# modbrainsv0_4_3.net
KiCad netlist of a schematic drawn in EAGLE
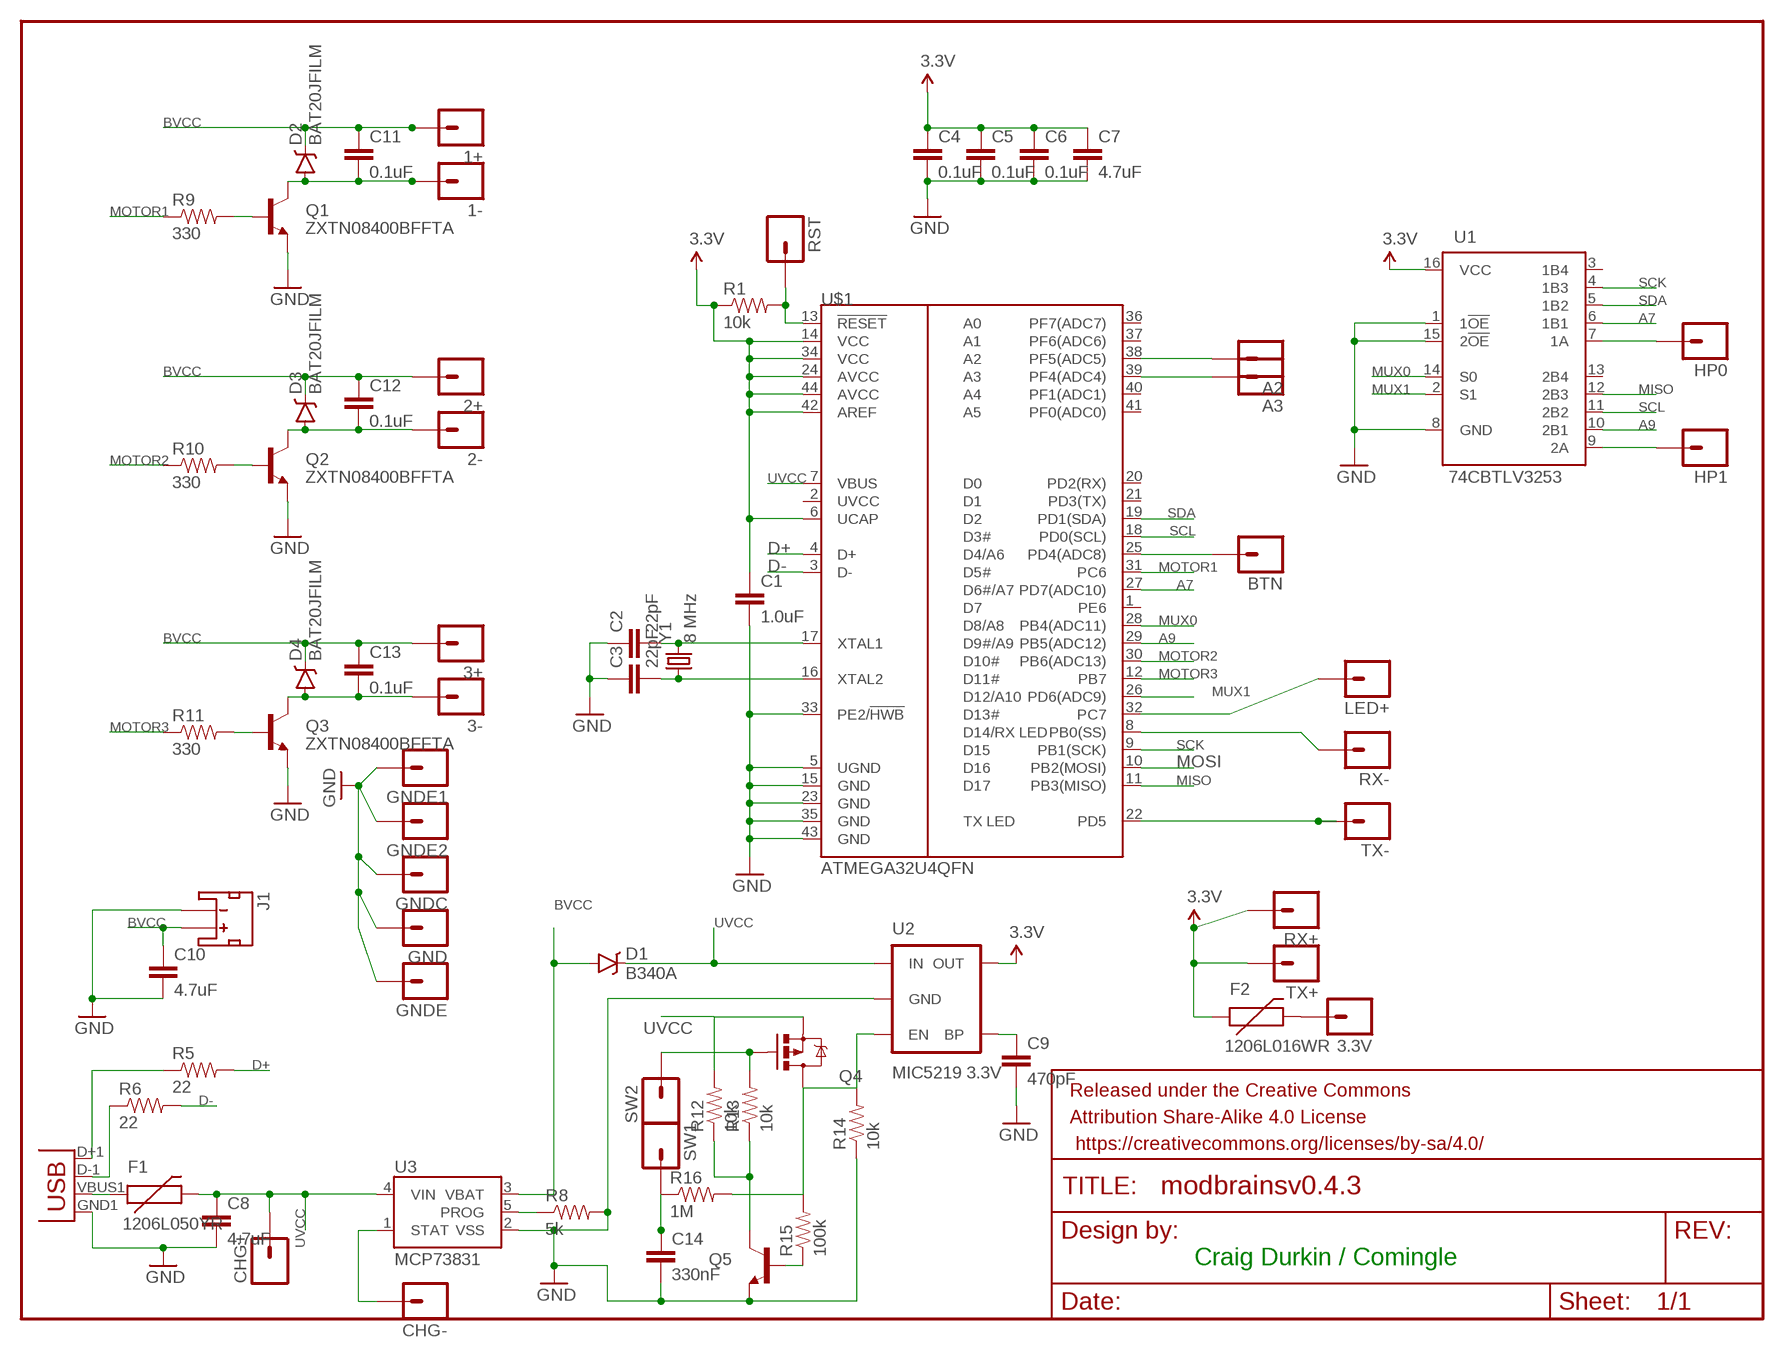
[diagram p0: schematic, sheet 1]

(export (version "E")
  (design (tool "Eeschema 10.0.6"))
  (components
    (comp (ref "1+")
      (value "M01PTH")
      (footprint "eagle-import:1X01")
      (libsource (lib "eagle-import") (part "M01PTH"))
    )
    (comp (ref "1-")
      (value "M01PTH")
      (footprint "eagle-import:1X01")
      (libsource (lib "eagle-import") (part "M01PTH"))
    )
    (comp (ref "2+")
      (value "M01PTH")
      (footprint "eagle-import:1X01")
      (libsource (lib "eagle-import") (part "M01PTH"))
    )
    (comp (ref "2-")
      (value "M01PTH")
      (footprint "eagle-import:1X01")
      (libsource (lib "eagle-import") (part "M01PTH"))
    )
    (comp (ref "3+")
      (value "M01PTH")
      (footprint "eagle-import:1X01")
      (libsource (lib "eagle-import") (part "M01PTH"))
    )
    (comp (ref "3-")
      (value "M01PTH")
      (footprint "eagle-import:1X01")
      (libsource (lib "eagle-import") (part "M01PTH"))
    )
    (comp (ref "3.3V")
      (value "M01PTH")
      (footprint "eagle-import:1X01")
      (libsource (lib "eagle-import") (part "M01PTH"))
    )
    (comp (ref "A2")
      (value "M01PTH")
      (footprint "eagle-import:1X01")
      (libsource (lib "eagle-import") (part "M01PTH"))
    )
    (comp (ref "A3")
      (value "M01PTH")
      (footprint "eagle-import:1X01")
      (libsource (lib "eagle-import") (part "M01PTH"))
    )
    (comp (ref "BTN")
      (value "M01PTH")
      (footprint "eagle-import:1X01")
      (libsource (lib "eagle-import") (part "M01PTH"))
    )
    (comp (ref "C1")
      (value "1.0uF")
      (footprint "eagle-import:0603-CAP")
      (libsource (lib "eagle-import") (part "CAP0603-CAP"))
    )
    (comp (ref "C2")
      (value "22pF")
      (footprint "eagle-import:0603-CAP")
      (libsource (lib "eagle-import") (part "CAP0603-CAP"))
    )
    (comp (ref "C3")
      (value "22pF")
      (footprint "eagle-import:0603-CAP")
      (libsource (lib "eagle-import") (part "CAP0603-CAP"))
    )
    (comp (ref "C4")
      (value "0.1uF")
      (footprint "eagle-import:0603-CAP")
      (libsource (lib "eagle-import") (part "SparkFun-Passives_CAP0603-CAP"))
    )
    (comp (ref "C5")
      (value "0.1uF")
      (footprint "eagle-import:0603-CAP")
      (libsource (lib "eagle-import") (part "SparkFun-Passives_CAP0603-CAP"))
    )
    (comp (ref "C6")
      (value "0.1uF")
      (footprint "eagle-import:0603-CAP")
      (libsource (lib "eagle-import") (part "SparkFun-Passives_CAP0603-CAP"))
    )
    (comp (ref "C7")
      (value "4.7uF")
      (footprint "eagle-import:0603-CAP")
      (libsource (lib "eagle-import") (part "SparkFun-Passives_CAP0603-CAP"))
    )
    (comp (ref "C8")
      (value "4.7uF")
      (footprint "eagle-import:1206")
      (libsource (lib "eagle-import") (part "SparkFun-Passives_CAP1206"))
    )
    (comp (ref "C9")
      (value "470pF")
      (footprint "eagle-import:0603-CAP")
      (libsource (lib "eagle-import") (part "CAP0603-CAP"))
    )
    (comp (ref "C10")
      (value "4.7uF")
      (footprint "eagle-import:1206")
      (libsource (lib "eagle-import") (part "SparkFun-Passives_CAP1206"))
    )
    (comp (ref "C11")
      (value "0.1uF")
      (footprint "eagle-import:0603-CAP")
      (libsource (lib "eagle-import") (part "CAP0603-CAP"))
    )
    (comp (ref "C12")
      (value "0.1uF")
      (footprint "eagle-import:0603-CAP")
      (libsource (lib "eagle-import") (part "CAP0603-CAP"))
    )
    (comp (ref "C13")
      (value "0.1uF")
      (footprint "eagle-import:0603-CAP")
      (libsource (lib "eagle-import") (part "CAP0603-CAP"))
    )
    (comp (ref "C14")
      (value "330nF")
      (footprint "eagle-import:0603-CAP")
      (libsource (lib "eagle-import") (part "CAP0603-CAP"))
    )
    (comp (ref "CHG+")
      (value "M01PTH")
      (footprint "eagle-import:1X01")
      (libsource (lib "eagle-import") (part "M01PTH"))
    )
    (comp (ref "CHG-")
      (value "M01PTH")
      (footprint "eagle-import:1X01")
      (libsource (lib "eagle-import") (part "M01PTH"))
    )
    (comp (ref "D1")
      (value "B340A")
      (footprint "eagle-import:SMA-DIODE")
      (libsource (lib "eagle-import") (part "DIODE-SCHOTTKY-B340A"))
    )
    (comp (ref "D2")
      (value "BAT20JFILM")
      (footprint "eagle-import:SOD-323")
      (libsource (lib "eagle-import") (part "BAT20JFILM"))
    )
    (comp (ref "D3")
      (value "BAT20JFILM")
      (footprint "eagle-import:SOD-323")
      (libsource (lib "eagle-import") (part "BAT20JFILM"))
    )
    (comp (ref "D4")
      (value "BAT20JFILM")
      (footprint "eagle-import:SOD-323")
      (libsource (lib "eagle-import") (part "BAT20JFILM"))
    )
    (comp (ref "F1")
      (value "1206L050YR")
      (footprint "eagle-import:PTC-1206")
      (libsource (lib "eagle-import") (part "PTCSMD"))
    )
    (comp (ref "F2")
      (value "1206L016WR")
      (footprint "eagle-import:PTC-1206")
      (libsource (lib "eagle-import") (part "PTCSMD"))
    )
    (comp (ref "FRAME1")
      (value "FRAME-LETTER")
      (footprint "eagle-import:CREATIVE_COMMONS")
      (libsource (lib "eagle-import") (part "FRAME-LETTER"))
    )
    (comp (ref "GND")
      (value "M01PTH")
      (footprint "eagle-import:1X01")
      (libsource (lib "eagle-import") (part "M01PTH"))
    )
    (comp (ref "GNDC")
      (value "M01PTH")
      (footprint "eagle-import:1X01")
      (libsource (lib "eagle-import") (part "M01PTH"))
    )
    (comp (ref "GNDE")
      (value "M01PTH")
      (footprint "eagle-import:1X01")
      (libsource (lib "eagle-import") (part "M01PTH"))
    )
    (comp (ref "GNDE1")
      (value "M01PTH")
      (footprint "eagle-import:1X01")
      (libsource (lib "eagle-import") (part "M01PTH"))
    )
    (comp (ref "GNDE2")
      (value "M01PTH")
      (footprint "eagle-import:1X01")
      (libsource (lib "eagle-import") (part "M01PTH"))
    )
    (comp (ref "HP0")
      (value "M01PTH")
      (footprint "eagle-import:1X01")
      (libsource (lib "eagle-import") (part "M01PTH"))
    )
    (comp (ref "HP1")
      (value "M01PTH")
      (footprint "eagle-import:1X01")
      (libsource (lib "eagle-import") (part "M01PTH"))
    )
    (comp (ref "J1")
      (value "JST_2MM_MALE")
      (footprint "eagle-import:JST-2-SMD")
      (libsource (lib "eagle-import") (part "JST_2MM_MALE"))
    )
    (comp (ref "JP4")
      (value "USB")
      (footprint "eagle-import:USB-B-MICRO-SMD_V03")
      (libsource (lib "eagle-import") (part "USB"))
    )
    (comp (ref "LED+")
      (value "M01PTH")
      (footprint "eagle-import:1X01")
      (libsource (lib "eagle-import") (part "M01PTH"))
    )
    (comp (ref "Q1")
      (value "ZXTN08400BFFTA")
      (footprint "eagle-import:SOT23-3")
      (libsource (lib "eagle-import") (part "TRANSISTOR_NPNSOT23-3"))
    )
    (comp (ref "Q2")
      (value "ZXTN08400BFFTA")
      (footprint "eagle-import:SOT23-3")
      (libsource (lib "eagle-import") (part "TRANSISTOR_NPNSOT23-3"))
    )
    (comp (ref "Q3")
      (value "ZXTN08400BFFTA")
      (footprint "eagle-import:SOT23-3")
      (libsource (lib "eagle-import") (part "TRANSISTOR_NPNSOT23-3"))
    )
    (comp (ref "Q4")
      (value "NTS2101PT1G")
      (footprint "eagle-import:SOT23-3")
      (libsource (lib "eagle-import") (part "MOSFET-PCHANNEL"))
    )
    (comp (ref "Q5")
      (value "MMBT2222A")
      (footprint "eagle-import:SOT23-3")
      (libsource (lib "eagle-import") (part "TRANSISTOR_NPNMMBT2222A"))
    )
    (comp (ref "R1")
      (value "10k")
      (footprint "eagle-import:0603-RES")
      (libsource (lib "eagle-import") (part "RESISTOR0603-RES"))
    )
    (comp (ref "R5")
      (value "22")
      (footprint "eagle-import:0603-RES")
      (libsource (lib "eagle-import") (part "RESISTOR0603-RES"))
    )
    (comp (ref "R6")
      (value "22")
      (footprint "eagle-import:0603-RES")
      (libsource (lib "eagle-import") (part "RESISTOR0603-RES"))
    )
    (comp (ref "R8")
      (value "5k")
      (footprint "eagle-import:0603-RES")
      (libsource (lib "eagle-import") (part "RESISTOR0603-RES"))
    )
    (comp (ref "R9")
      (value "330")
      (footprint "eagle-import:0603-RES")
      (libsource (lib "eagle-import") (part "RESISTOR0603-RES"))
    )
    (comp (ref "R10")
      (value "330")
      (footprint "eagle-import:0603-RES")
      (libsource (lib "eagle-import") (part "RESISTOR0603-RES"))
    )
    (comp (ref "R11")
      (value "330")
      (footprint "eagle-import:0603-RES")
      (libsource (lib "eagle-import") (part "RESISTOR0603-RES"))
    )
    (comp (ref "R12")
      (value "10k")
      (footprint "eagle-import:0603-RES")
      (libsource (lib "eagle-import") (part "RESISTOR0603-RES"))
    )
    (comp (ref "R13")
      (value "10k")
      (footprint "eagle-import:0603-RES")
      (libsource (lib "eagle-import") (part "RESISTOR0603-RES"))
    )
    (comp (ref "R14")
      (value "10k")
      (footprint "eagle-import:0603-RES")
      (libsource (lib "eagle-import") (part "RESISTOR0603-RES"))
    )
    (comp (ref "R15")
      (value "100k")
      (footprint "eagle-import:0603-RES")
      (libsource (lib "eagle-import") (part "RESISTOR0603-RES"))
    )
    (comp (ref "R16")
      (value "1M")
      (footprint "eagle-import:0603-RES")
      (libsource (lib "eagle-import") (part "RESISTOR0603-RES"))
    )
    (comp (ref "RST")
      (value "M01PTH")
      (footprint "eagle-import:1X01")
      (libsource (lib "eagle-import") (part "M01PTH"))
    )
    (comp (ref "RX+")
      (value "M01PTH")
      (footprint "eagle-import:1X01")
      (libsource (lib "eagle-import") (part "M01PTH"))
    )
    (comp (ref "RX-")
      (value "M01PTH")
      (footprint "eagle-import:1X01")
      (libsource (lib "eagle-import") (part "M01PTH"))
    )
    (comp (ref "SW1")
      (value "M01PTH")
      (footprint "eagle-import:1X01")
      (libsource (lib "eagle-import") (part "M01PTH"))
    )
    (comp (ref "SW2")
      (value "M01PTH")
      (footprint "eagle-import:1X01")
      (libsource (lib "eagle-import") (part "M01PTH"))
    )
    (comp (ref "TX+")
      (value "M01PTH")
      (footprint "eagle-import:1X01")
      (libsource (lib "eagle-import") (part "M01PTH"))
    )
    (comp (ref "TX-")
      (value "M01PTH")
      (footprint "eagle-import:1X01")
      (libsource (lib "eagle-import") (part "M01PTH"))
    )
    (comp (ref "U$1")
      (value "ATMEGA32U4QFN")
      (footprint "eagle-import:QFN-44")
      (libsource (lib "eagle-import") (part "ATMEGA32U4QFN"))
    )
    (comp (ref "U1")
      (value "74CBTLV3253")
      (footprint "eagle-import:SSOP16-PRACTICE")
      (libsource (lib "eagle-import") (part "74CBTLV3253"))
    )
    (comp (ref "U2")
      (value "MIC5219 3.3V")
      (footprint "eagle-import:SOT23-5")
      (libsource (lib "eagle-import") (part "V_REG_MIC52193.3V"))
    )
    (comp (ref "U3")
      (value "MCP73831")
      (footprint "eagle-import:SOT23-5")
      (libsource (lib "eagle-import") (part "MCP73831"))
    )
    (comp (ref "Y1")
      (value "8 MHz")
      (footprint "eagle-import:CRYSTAL-SMD-5X3")
      (libsource (lib "eagle-import") (part "CRYSTAL5X3"))
    )
  )
  (nets
    (net (code "1") (name "/A7") (class "Default")
      (node (ref "U$1") (pin "27") (pinfunction "PD7(ADC10)_27") (pintype "bidirectional"))
      (node (ref "U1") (pin "6") (pinfunction "1B1_6") (pintype "bidirectional"))
    )
    (net (code "2") (name "/A9") (class "Default")
      (node (ref "U$1") (pin "29") (pinfunction "PB5(ADC12)_29") (pintype "bidirectional"))
      (node (ref "U1") (pin "10") (pinfunction "2B1_10") (pintype "bidirectional"))
    )
    (net (code "3") (name "/BVCC") (class "Default")
      (node (ref "1+") (pin "1") (pinfunction "1_1") (pintype "passive"))
      (node (ref "2+") (pin "1") (pinfunction "1_1") (pintype "passive"))
      (node (ref "3+") (pin "1") (pinfunction "1_1") (pintype "passive"))
      (node (ref "C10") (pin "1") (pinfunction "1_1") (pintype "passive"))
      (node (ref "C11") (pin "1") (pinfunction "1_1") (pintype "passive"))
      (node (ref "C12") (pin "1") (pinfunction "1_1") (pintype "passive"))
      (node (ref "C13") (pin "1") (pinfunction "1_1") (pintype "passive"))
      (node (ref "D1") (pin "A") (pinfunction "A_A") (pintype "passive"))
      (node (ref "D2") (pin "C") (pinfunction "C_C") (pintype "passive"))
      (node (ref "D3") (pin "C") (pinfunction "C_C") (pintype "passive"))
      (node (ref "D4") (pin "C") (pinfunction "C_C") (pintype "passive"))
      (node (ref "J1") (pin "2") (pinfunction "+_2") (pintype "bidirectional"))
      (node (ref "U3") (pin "3") (pinfunction "VBAT_3") (pintype "power_in"))
    )
    (net (code "4") (name "/D+") (class "Default")
      (node (ref "R5") (pin "2") (pinfunction "2_2") (pintype "passive"))
      (node (ref "U$1") (pin "4") (pinfunction "D+_4") (pintype "bidirectional"))
    )
    (net (code "5") (name "/D-") (class "Default")
      (node (ref "R6") (pin "2") (pinfunction "2_2") (pintype "passive"))
      (node (ref "U$1") (pin "3") (pinfunction "D-_3") (pintype "bidirectional"))
    )
    (net (code "6") (name "/MISO") (class "Default")
      (node (ref "U$1") (pin "11") (pinfunction "PB3(MISO)_11") (pintype "bidirectional"))
      (node (ref "U1") (pin "12") (pinfunction "2B3_12") (pintype "bidirectional"))
    )
    (net (code "7") (name "/MOSI") (class "Default")
      (node (ref "U$1") (pin "10") (pinfunction "PB2(MOSI)_10") (pintype "bidirectional"))
    )
    (net (code "8") (name "/MOTOR1") (class "Default")
      (node (ref "R9") (pin "1") (pinfunction "1_1") (pintype "passive"))
      (node (ref "U$1") (pin "31") (pinfunction "PC6_31") (pintype "bidirectional"))
    )
    (net (code "9") (name "/MOTOR2") (class "Default")
      (node (ref "R10") (pin "1") (pinfunction "1_1") (pintype "passive"))
      (node (ref "U$1") (pin "30") (pinfunction "PB6(ADC13)_30") (pintype "bidirectional"))
    )
    (net (code "10") (name "/MOTOR3") (class "Default")
      (node (ref "R11") (pin "1") (pinfunction "1_1") (pintype "passive"))
      (node (ref "U$1") (pin "12") (pinfunction "PB7_12") (pintype "bidirectional"))
    )
    (net (code "11") (name "/MUX0") (class "Default")
      (node (ref "U$1") (pin "28") (pinfunction "PB4(ADC11)_28") (pintype "bidirectional"))
      (node (ref "U1") (pin "14") (pinfunction "S0_14") (pintype "bidirectional"))
    )
    (net (code "12") (name "/MUX1") (class "Default")
      (node (ref "U$1") (pin "26") (pinfunction "PD6(ADC9)_26") (pintype "bidirectional"))
      (node (ref "U1") (pin "2") (pinfunction "S1_2") (pintype "bidirectional"))
    )
    (net (code "13") (name "/SCK") (class "Default")
      (node (ref "U$1") (pin "9") (pinfunction "PB1(SCK)_9") (pintype "bidirectional"))
      (node (ref "U1") (pin "4") (pinfunction "1B3_4") (pintype "bidirectional"))
    )
    (net (code "14") (name "/SCL") (class "Default")
      (node (ref "U$1") (pin "18") (pinfunction "PD0(SCL)_18") (pintype "bidirectional"))
      (node (ref "U1") (pin "11") (pinfunction "2B2_11") (pintype "bidirectional"))
    )
    (net (code "15") (name "/SDA") (class "Default")
      (node (ref "U$1") (pin "19") (pinfunction "PD1(SDA)_19") (pintype "bidirectional"))
      (node (ref "U1") (pin "5") (pinfunction "1B2_5") (pintype "bidirectional"))
    )
    (net (code "16") (name "/UVCC") (class "Default")
      (node (ref "C8") (pin "1") (pinfunction "1_1") (pintype "passive"))
      (node (ref "CHG+") (pin "1") (pinfunction "1_1") (pintype "passive"))
      (node (ref "D1") (pin "C") (pinfunction "C_C") (pintype "passive"))
      (node (ref "F1") (pin "2") (pinfunction "2_2") (pintype "bidirectional"))
      (node (ref "Q4") (pin "2") (pinfunction "S_2") (pintype "passive"))
      (node (ref "R12") (pin "2") (pinfunction "2_2") (pintype "passive"))
      (node (ref "U$1") (pin "7") (pinfunction "VBUS_7") (pintype "bidirectional"))
      (node (ref "U2") (pin "1") (pinfunction "IN_1") (pintype "input"))
      (node (ref "U3") (pin "4") (pinfunction "VIN_4") (pintype "power_in"))
    )
    (net (code "17") (name "3.3V") (class "Default")
      (node (ref "C1") (pin "1") (pinfunction "1_1") (pintype "passive"))
      (node (ref "C4") (pin "1") (pinfunction "1_1") (pintype "passive"))
      (node (ref "C5") (pin "1") (pinfunction "1_1") (pintype "passive"))
      (node (ref "C6") (pin "1") (pinfunction "1_1") (pintype "passive"))
      (node (ref "C7") (pin "1") (pinfunction "1_1") (pintype "passive"))
      (node (ref "F2") (pin "1") (pinfunction "1_1") (pintype "bidirectional"))
      (node (ref "R1") (pin "1") (pinfunction "1_1") (pintype "passive"))
      (node (ref "RX+") (pin "1") (pinfunction "1_1") (pintype "passive"))
      (node (ref "TX+") (pin "1") (pinfunction "1_1") (pintype "passive"))
      (node (ref "U$1") (pin "14") (pinfunction "VCC_14") (pintype "bidirectional"))
      (node (ref "U$1") (pin "24") (pinfunction "AVCC_24") (pintype "bidirectional"))
      (node (ref "U$1") (pin "34") (pinfunction "VCC_34") (pintype "bidirectional"))
      (node (ref "U$1") (pin "42") (pinfunction "AREF_42") (pintype "bidirectional"))
      (node (ref "U$1") (pin "44") (pinfunction "AVCC_44") (pintype "bidirectional"))
      (node (ref "U$1") (pin "6") (pinfunction "UCAP_6") (pintype "bidirectional"))
      (node (ref "U1") (pin "16") (pinfunction "VCC_16") (pintype "power_in"))
      (node (ref "U2") (pin "5") (pinfunction "OUT_5") (pintype "passive"))
    )
    (net (code "18") (name "GND") (class "Default")
      (node (ref "C1") (pin "2") (pinfunction "2_2") (pintype "passive"))
      (node (ref "C10") (pin "2") (pinfunction "2_2") (pintype "passive"))
      (node (ref "C14") (pin "2") (pinfunction "2_2") (pintype "passive"))
      (node (ref "C2") (pin "1") (pinfunction "1_1") (pintype "passive"))
      (node (ref "C3") (pin "1") (pinfunction "1_1") (pintype "passive"))
      (node (ref "C4") (pin "2") (pinfunction "2_2") (pintype "passive"))
      (node (ref "C5") (pin "2") (pinfunction "2_2") (pintype "passive"))
      (node (ref "C6") (pin "2") (pinfunction "2_2") (pintype "passive"))
      (node (ref "C7") (pin "2") (pinfunction "2_2") (pintype "passive"))
      (node (ref "C8") (pin "2") (pinfunction "2_2") (pintype "passive"))
      (node (ref "C9") (pin "2") (pinfunction "2_2") (pintype "passive"))
      (node (ref "GND") (pin "1") (pinfunction "1_1") (pintype "passive"))
      (node (ref "GNDC") (pin "1") (pinfunction "1_1") (pintype "passive"))
      (node (ref "GNDE") (pin "1") (pinfunction "1_1") (pintype "passive"))
      (node (ref "GNDE1") (pin "1") (pinfunction "1_1") (pintype "passive"))
      (node (ref "GNDE2") (pin "1") (pinfunction "1_1") (pintype "passive"))
      (node (ref "J1") (pin "1") (pinfunction "-_1") (pintype "bidirectional"))
      (node (ref "JP4") (pin "GND1") (pinfunction "GND_GND1") (pintype "bidirectional"))
      (node (ref "Q1") (pin "2") (pinfunction "E_2") (pintype "passive"))
      (node (ref "Q2") (pin "2") (pinfunction "E_2") (pintype "passive"))
      (node (ref "Q3") (pin "2") (pinfunction "E_2") (pintype "passive"))
      (node (ref "Q5") (pin "2") (pinfunction "E_2") (pintype "passive"))
      (node (ref "R14") (pin "1") (pinfunction "1_1") (pintype "passive"))
      (node (ref "R8") (pin "2") (pinfunction "2_2") (pintype "passive"))
      (node (ref "U$1") (pin "15") (pinfunction "GND_15") (pintype "bidirectional"))
      (node (ref "U$1") (pin "23") (pinfunction "GND_23") (pintype "bidirectional"))
      (node (ref "U$1") (pin "33") (pinfunction "PE2/~{HWB}_33") (pintype "bidirectional"))
      (node (ref "U$1") (pin "35") (pinfunction "GND_35") (pintype "bidirectional"))
      (node (ref "U$1") (pin "43") (pinfunction "GND_43") (pintype "bidirectional"))
      (node (ref "U$1") (pin "5") (pinfunction "UGND_5") (pintype "bidirectional"))
      (node (ref "U1") (pin "1") (pinfunction "1~{OE}_1") (pintype "input"))
      (node (ref "U1") (pin "15") (pinfunction "2~{OE}_15") (pintype "input"))
      (node (ref "U1") (pin "8") (pinfunction "GND_8") (pintype "power_in"))
      (node (ref "U2") (pin "2") (pinfunction "GND_2") (pintype "input"))
      (node (ref "U3") (pin "2") (pinfunction "VSS_2") (pintype "power_in"))
    )
    (net (code "19") (name "Net-(3.3V-Pad1)") (class "Default")
      (node (ref "3.3V") (pin "1") (pinfunction "1_1") (pintype "passive"))
      (node (ref "F2") (pin "2") (pinfunction "2_2") (pintype "bidirectional"))
    )
    (net (code "20") (name "Net-(C14-Pad1)") (class "Default")
      (node (ref "C14") (pin "1") (pinfunction "1_1") (pintype "passive"))
      (node (ref "R16") (pin "1") (pinfunction "1_1") (pintype "passive"))
      (node (ref "SW1") (pin "1") (pinfunction "1_1") (pintype "passive"))
    )
    (net (code "21") (name "Net-(JP4-D+)") (class "Default")
      (node (ref "JP4") (pin "D+1") (pinfunction "D+_D+1") (pintype "bidirectional"))
      (node (ref "R5") (pin "1") (pinfunction "1_1") (pintype "passive"))
    )
    (net (code "22") (name "Net-(JP4-D-)") (class "Default")
      (node (ref "JP4") (pin "D-1") (pinfunction "D-_D-1") (pintype "bidirectional"))
      (node (ref "R6") (pin "1") (pinfunction "1_1") (pintype "passive"))
    )
    (net (code "23") (name "Net-(JP4-VBUS)") (class "Default")
      (node (ref "F1") (pin "1") (pinfunction "1_1") (pintype "bidirectional"))
      (node (ref "JP4") (pin "VBUS1") (pinfunction "VBUS_VBUS1") (pintype "bidirectional"))
    )
    (net (code "24") (name "Net-(Q1-B)") (class "Default")
      (node (ref "Q1") (pin "1") (pinfunction "B_1") (pintype "passive"))
      (node (ref "R9") (pin "2") (pinfunction "2_2") (pintype "passive"))
    )
    (net (code "25") (name "Net-(Q1-C)") (class "Default")
      (node (ref "1-") (pin "1") (pinfunction "1_1") (pintype "passive"))
      (node (ref "C11") (pin "2") (pinfunction "2_2") (pintype "passive"))
      (node (ref "D2") (pin "A") (pinfunction "A_A") (pintype "passive"))
      (node (ref "Q1") (pin "3") (pinfunction "C_3") (pintype "passive"))
    )
    (net (code "26") (name "Net-(Q2-B)") (class "Default")
      (node (ref "Q2") (pin "1") (pinfunction "B_1") (pintype "passive"))
      (node (ref "R10") (pin "2") (pinfunction "2_2") (pintype "passive"))
    )
    (net (code "27") (name "Net-(Q2-C)") (class "Default")
      (node (ref "2-") (pin "1") (pinfunction "1_1") (pintype "passive"))
      (node (ref "C12") (pin "2") (pinfunction "2_2") (pintype "passive"))
      (node (ref "D3") (pin "A") (pinfunction "A_A") (pintype "passive"))
      (node (ref "Q2") (pin "3") (pinfunction "C_3") (pintype "passive"))
    )
    (net (code "28") (name "Net-(Q3-B)") (class "Default")
      (node (ref "Q3") (pin "1") (pinfunction "B_1") (pintype "passive"))
      (node (ref "R11") (pin "2") (pinfunction "2_2") (pintype "passive"))
    )
    (net (code "29") (name "Net-(Q3-C)") (class "Default")
      (node (ref "3-") (pin "1") (pinfunction "1_1") (pintype "passive"))
      (node (ref "C13") (pin "2") (pinfunction "2_2") (pintype "passive"))
      (node (ref "D4") (pin "A") (pinfunction "A_A") (pintype "passive"))
      (node (ref "Q3") (pin "3") (pinfunction "C_3") (pintype "passive"))
    )
    (net (code "30") (name "Net-(Q4-D)") (class "Default")
      (node (ref "Q4") (pin "3") (pinfunction "D_3") (pintype "passive"))
      (node (ref "R14") (pin "2") (pinfunction "2_2") (pintype "passive"))
      (node (ref "R15") (pin "2") (pinfunction "2_2") (pintype "passive"))
      (node (ref "R16") (pin "2") (pinfunction "2_2") (pintype "passive"))
      (node (ref "U2") (pin "3") (pinfunction "EN_3") (pintype "input"))
    )
    (net (code "31") (name "Net-(Q4-G)") (class "Default")
      (node (ref "Q4") (pin "1") (pinfunction "G_1") (pintype "passive"))
      (node (ref "R13") (pin "2") (pinfunction "2_2") (pintype "passive"))
      (node (ref "SW2") (pin "1") (pinfunction "1_1") (pintype "passive"))
    )
    (net (code "32") (name "Net-(Q5-B)") (class "Default")
      (node (ref "Q5") (pin "1") (pinfunction "B_1") (pintype "passive"))
      (node (ref "R15") (pin "1") (pinfunction "1_1") (pintype "passive"))
    )
    (net (code "33") (name "Net-(Q5-C)") (class "Default")
      (node (ref "Q5") (pin "3") (pinfunction "C_3") (pintype "passive"))
      (node (ref "R12") (pin "1") (pinfunction "1_1") (pintype "passive"))
      (node (ref "R13") (pin "1") (pinfunction "1_1") (pintype "passive"))
    )
    (net (code "34") (name "Net-(U$1-PB0(SS))") (class "Default")
      (node (ref "RX-") (pin "1") (pinfunction "1_1") (pintype "passive"))
      (node (ref "U$1") (pin "8") (pinfunction "PB0(SS)_8") (pintype "bidirectional"))
    )
    (net (code "35") (name "Net-(U$1-PC7)") (class "Default")
      (node (ref "LED+") (pin "1") (pinfunction "1_1") (pintype "passive"))
      (node (ref "U$1") (pin "32") (pinfunction "PC7_32") (pintype "bidirectional"))
    )
    (net (code "36") (name "Net-(U$1-PD4(ADC8))") (class "Default")
      (node (ref "BTN") (pin "1") (pinfunction "1_1") (pintype "passive"))
      (node (ref "U$1") (pin "25") (pinfunction "PD4(ADC8)_25") (pintype "bidirectional"))
    )
    (net (code "37") (name "Net-(U$1-PD5)") (class "Default")
      (node (ref "TX-") (pin "1") (pinfunction "1_1") (pintype "passive"))
      (node (ref "U$1") (pin "22") (pinfunction "PD5_22") (pintype "bidirectional"))
    )
    (net (code "38") (name "Net-(U$1-PF4(ADC4))") (class "Default")
      (node (ref "A3") (pin "1") (pinfunction "1_1") (pintype "passive"))
      (node (ref "U$1") (pin "39") (pinfunction "PF4(ADC4)_39") (pintype "bidirectional"))
    )
    (net (code "39") (name "Net-(U$1-PF5(ADC5))") (class "Default")
      (node (ref "A2") (pin "1") (pinfunction "1_1") (pintype "passive"))
      (node (ref "U$1") (pin "38") (pinfunction "PF5(ADC5)_38") (pintype "bidirectional"))
    )
    (net (code "40") (name "Net-(U$1-XTAL1)") (class "Default")
      (node (ref "C2") (pin "2") (pinfunction "2_2") (pintype "passive"))
      (node (ref "U$1") (pin "17") (pinfunction "XTAL1_17") (pintype "bidirectional"))
      (node (ref "Y1") (pin "3") (pinfunction "2_3") (pintype "passive"))
    )
    (net (code "41") (name "Net-(U$1-XTAL2)") (class "Default")
      (node (ref "C3") (pin "2") (pinfunction "2_2") (pintype "passive"))
      (node (ref "U$1") (pin "16") (pinfunction "XTAL2_16") (pintype "bidirectional"))
      (node (ref "Y1") (pin "1") (pinfunction "1_1") (pintype "passive"))
    )
    (net (code "42") (name "Net-(U$1-~{RESET})") (class "Default")
      (node (ref "R1") (pin "2") (pinfunction "2_2") (pintype "passive"))
      (node (ref "RST") (pin "1") (pinfunction "1_1") (pintype "passive"))
      (node (ref "U$1") (pin "13") (pinfunction "~{RESET}_13") (pintype "bidirectional"))
    )
    (net (code "43") (name "Net-(U1-1A)") (class "Default")
      (node (ref "HP0") (pin "1") (pinfunction "1_1") (pintype "passive"))
      (node (ref "U1") (pin "7") (pinfunction "1A_7") (pintype "bidirectional"))
    )
    (net (code "44") (name "Net-(U1-2A)") (class "Default")
      (node (ref "HP1") (pin "1") (pinfunction "1_1") (pintype "passive"))
      (node (ref "U1") (pin "9") (pinfunction "2A_9") (pintype "bidirectional"))
    )
    (net (code "45") (name "Net-(U2-BP)") (class "Default")
      (node (ref "C9") (pin "1") (pinfunction "1_1") (pintype "passive"))
      (node (ref "U2") (pin "4") (pinfunction "BP_4") (pintype "input"))
    )
    (net (code "46") (name "Net-(U3-PROG)") (class "Default")
      (node (ref "R8") (pin "1") (pinfunction "1_1") (pintype "passive"))
      (node (ref "U3") (pin "5") (pinfunction "PROG_5") (pintype "bidirectional"))
    )
    (net (code "47") (name "Net-(U3-STAT)") (class "Default")
      (node (ref "CHG-") (pin "1") (pinfunction "1_1") (pintype "passive"))
      (node (ref "U3") (pin "1") (pinfunction "STAT_1") (pintype "output"))
    )
    (net (code "48") (name "unconnected-(J1-PAD1-PadNC1)") (class "Default")
      (node (ref "J1") (pin "NC1") (pinfunction "PAD1_NC1") (pintype "bidirectional"))
    )
    (net (code "49") (name "unconnected-(J1-PAD2-PadNC2)") (class "Default")
      (node (ref "J1") (pin "NC2") (pinfunction "PAD2_NC2") (pintype "bidirectional"))
    )
    (net (code "50") (name "unconnected-(U$1-PD2(RX)-Pad20)") (class "Default")
      (node (ref "U$1") (pin "20") (pinfunction "PD2(RX)_20") (pintype "bidirectional"))
    )
    (net (code "51") (name "unconnected-(U$1-PD3(TX)-Pad21)") (class "Default")
      (node (ref "U$1") (pin "21") (pinfunction "PD3(TX)_21") (pintype "bidirectional"))
    )
    (net (code "52") (name "unconnected-(U$1-PE6-Pad1)") (class "Default")
      (node (ref "U$1") (pin "1") (pinfunction "PE6_1") (pintype "bidirectional"))
    )
    (net (code "53") (name "unconnected-(U$1-PF0(ADC0)-Pad41)") (class "Default")
      (node (ref "U$1") (pin "41") (pinfunction "PF0(ADC0)_41") (pintype "bidirectional"))
    )
    (net (code "54") (name "unconnected-(U$1-PF1(ADC1)-Pad40)") (class "Default")
      (node (ref "U$1") (pin "40") (pinfunction "PF1(ADC1)_40") (pintype "bidirectional"))
    )
    (net (code "55") (name "unconnected-(U$1-PF6(ADC6)-Pad37)") (class "Default")
      (node (ref "U$1") (pin "37") (pinfunction "PF6(ADC6)_37") (pintype "bidirectional"))
    )
    (net (code "56") (name "unconnected-(U$1-PF7(ADC7)-Pad36)") (class "Default")
      (node (ref "U$1") (pin "36") (pinfunction "PF7(ADC7)_36") (pintype "bidirectional"))
    )
    (net (code "57") (name "unconnected-(U$1-UVCC-Pad2)") (class "Default")
      (node (ref "U$1") (pin "2") (pinfunction "UVCC_2") (pintype "bidirectional"))
    )
    (net (code "58") (name "unconnected-(U1-1B4-Pad3)") (class "Default")
      (node (ref "U1") (pin "3") (pinfunction "1B4_3") (pintype "bidirectional"))
    )
    (net (code "59") (name "unconnected-(U1-2B4-Pad13)") (class "Default")
      (node (ref "U1") (pin "13") (pinfunction "2B4_13") (pintype "bidirectional"))
    )
  )
)
